# 24LC256.net
KiCad netlist of a schematic drawn in EAGLE
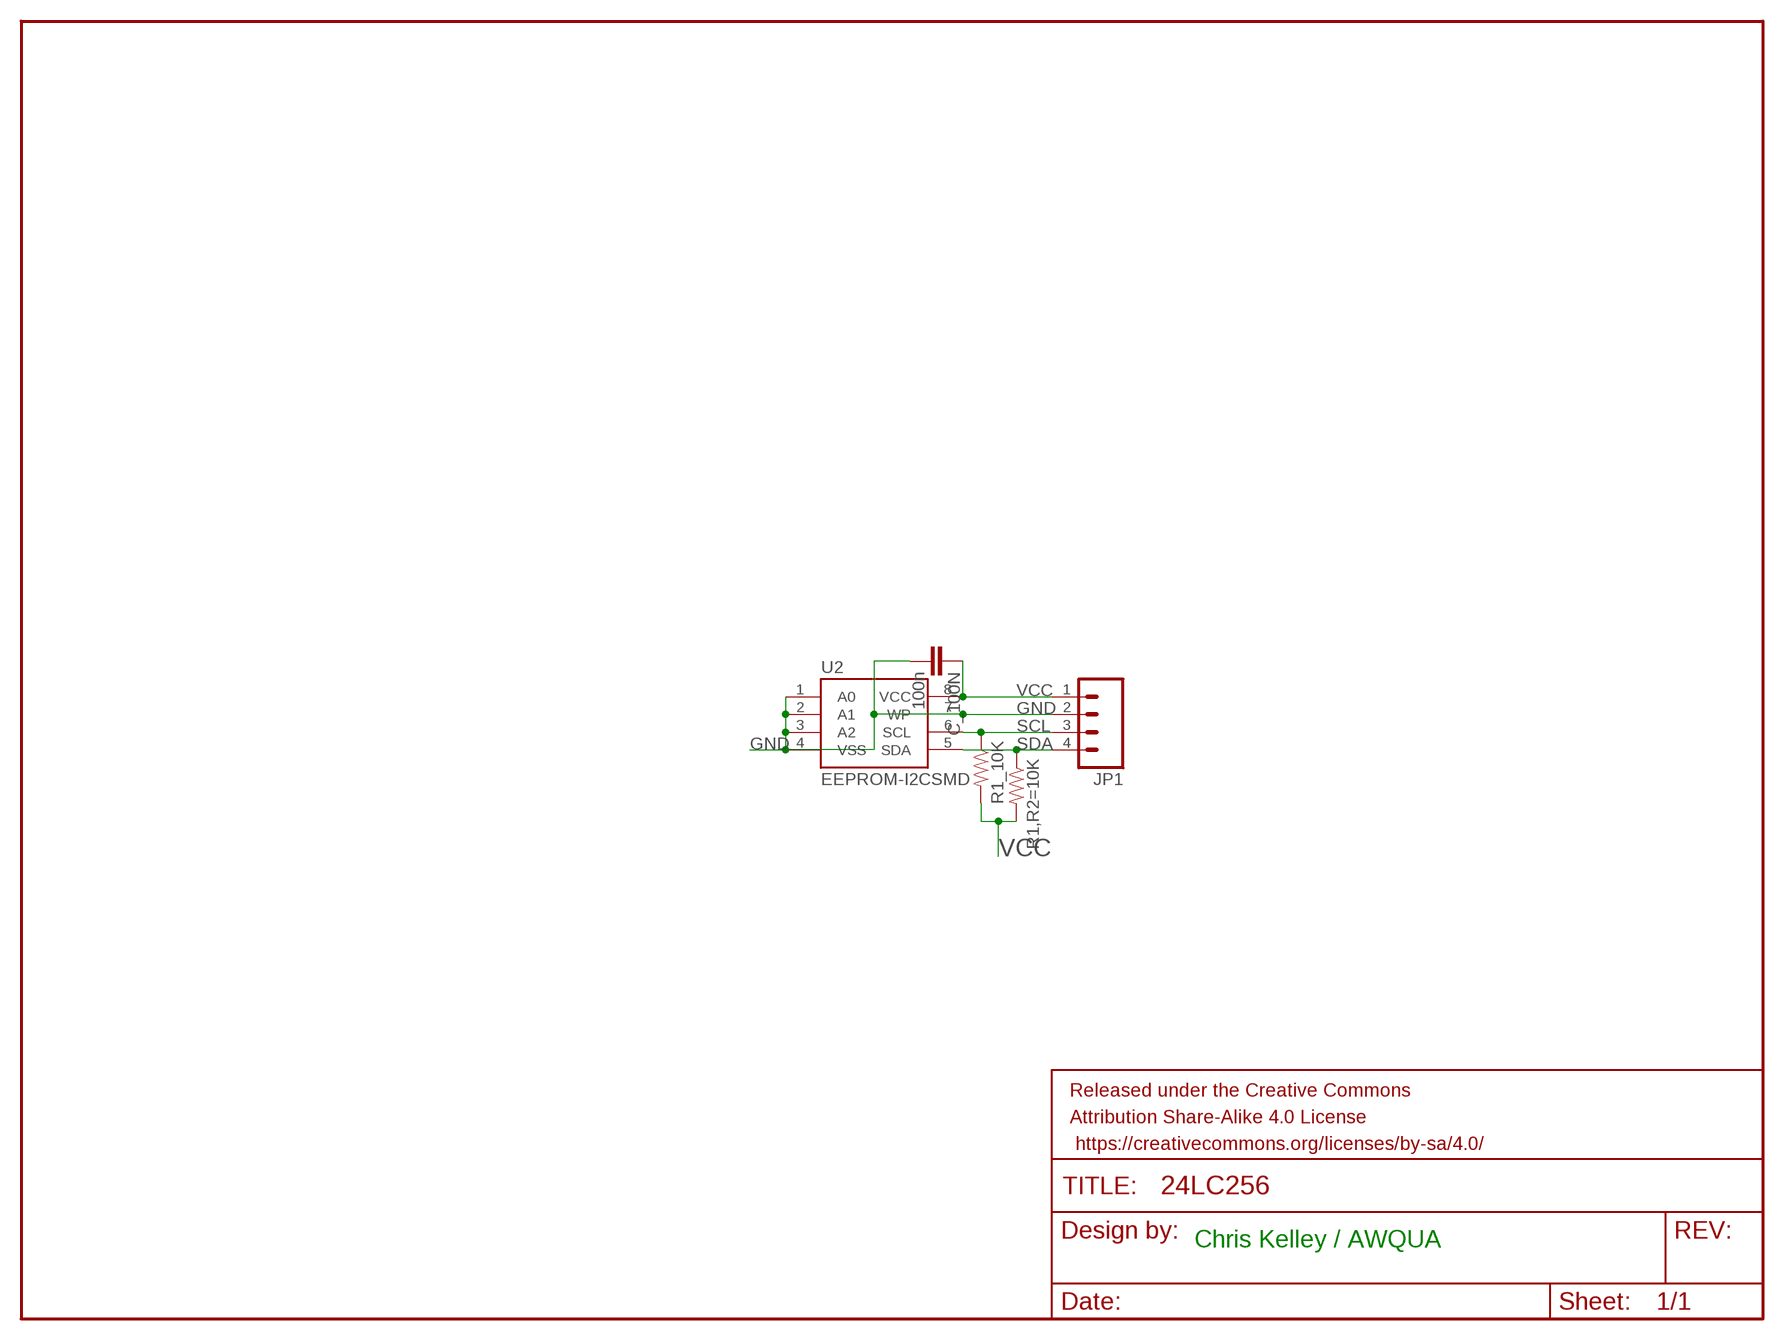
[diagram p0: schematic, sheet 1]

(export (version "E")
  (design (tool "Eeschema 10.0.6"))
  (components
    (comp (ref "C_100N")
      (value "100n")
      (footprint "eagle-import:0603-CAP")
      (libsource (lib "eagle-import") (part "CAP0603-CAP"))
    )
    (comp (ref "FRAME1")
      (value "FRAME-LETTER")
      (footprint "eagle-import:CREATIVE_COMMONS")
      (libsource (lib "eagle-import") (part "FRAME-LETTER"))
    )
    (comp (ref "JP1")
      (value "M04PTH")
      (footprint "eagle-import:1X04")
      (libsource (lib "eagle-import") (part "M04PTH"))
    )
    (comp (ref "R1,R2=10K")
      (value "RESISTOR0603-RES")
      (footprint "eagle-import:0603-RES")
      (libsource (lib "eagle-import") (part "RESISTOR0603-RES"))
    )
    (comp (ref "R1_10K")
      (value "RESISTOR0603-RES")
      (footprint "eagle-import:0603-RES")
      (libsource (lib "eagle-import") (part "RESISTOR0603-RES"))
    )
    (comp (ref "U2")
      (value "EEPROM-I2CSMD")
      (footprint "eagle-import:SO08")
      (libsource (lib "eagle-import") (part "EEPROM-I2CSMD"))
    )
  )
  (nets
    (net (code "1") (name "/GND") (class "Default")
      (node (ref "C_100N") (pin "2") (pinfunction "2_2") (pintype "passive"))
      (node (ref "JP1") (pin "2") (pinfunction "2_2") (pintype "passive"))
      (node (ref "U2") (pin "1") (pinfunction "A0_1") (pintype "bidirectional"))
      (node (ref "U2") (pin "2") (pinfunction "A1_2") (pintype "bidirectional"))
      (node (ref "U2") (pin "3") (pinfunction "A2_3") (pintype "bidirectional"))
      (node (ref "U2") (pin "4") (pinfunction "VSS_4") (pintype "power_in"))
      (node (ref "U2") (pin "7") (pinfunction "WP_7") (pintype "bidirectional"))
    )
    (net (code "2") (name "/SCL") (class "Default")
      (node (ref "JP1") (pin "3") (pinfunction "3_3") (pintype "passive"))
      (node (ref "R1_10K") (pin "1") (pinfunction "1_1") (pintype "passive"))
      (node (ref "U2") (pin "6") (pinfunction "SCL_6") (pintype "bidirectional"))
    )
    (net (code "3") (name "/SDA") (class "Default")
      (node (ref "JP1") (pin "4") (pinfunction "4_4") (pintype "passive"))
      (node (ref "R1,R2=10K") (pin "1") (pinfunction "1_1") (pintype "passive"))
      (node (ref "U2") (pin "5") (pinfunction "SDA_5") (pintype "bidirectional"))
    )
    (net (code "4") (name "/VCC") (class "Default")
      (node (ref "C_100N") (pin "1") (pinfunction "1_1") (pintype "passive"))
      (node (ref "JP1") (pin "1") (pinfunction "1_1") (pintype "passive"))
      (node (ref "R1,R2=10K") (pin "2") (pinfunction "2_2") (pintype "passive"))
      (node (ref "R1_10K") (pin "2") (pinfunction "2_2") (pintype "passive"))
      (node (ref "U2") (pin "8") (pinfunction "VCC_8") (pintype "power_in"))
    )
  )
)
